# FT232.net
KiCad netlist of a schematic drawn in Altium Designer
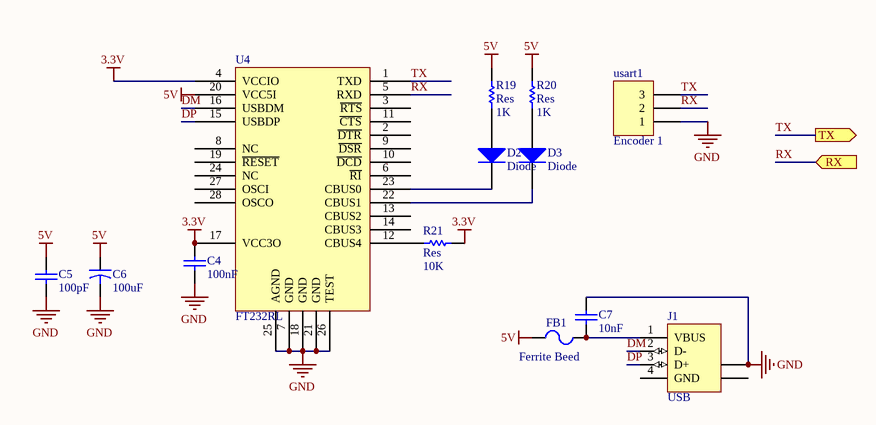
[diagram p0: FT232.SchDoc]

(export (version "E")
  (design (tool "Eeschema 10.0.6"))
  (components
    (comp (ref "C4")
      (value "100nF")
      (footprint "2012[0805]")
      (description "Capacitor")
      (fields (field (name "Comment") "Cap_UP") (field (name "PUBLISHER") "Altium Limited"))
      (libsource (lib "KN2CLib") (part "Cap_UP"))
    )
    (comp (ref "C5")
      (value "100pF")
      (footprint "2012[0805]")
      (description "Capacitor")
      (fields (field (name "Comment") "Cap_UP") (field (name "PUBLISHER") "Altium Limited"))
      (libsource (lib "KN2CLib") (part "Cap_UP"))
    )
    (comp (ref "C6")
      (value "100uF")
      (footprint "7343")
      (description "Capacitor")
      (fields (field (name "Comment") "Cap_El") (field (name "PUBLISHER") "Altium Limited"))
      (libsource (lib "KN2CLib") (part "Cap_El"))
    )
    (comp (ref "C7")
      (value "10nF")
      (footprint "2012[0805]")
      (description "Capacitor")
      (fields (field (name "Comment") "Cap_UP") (field (name "PUBLISHER") "Altium Limited"))
      (libsource (lib "KN2CLib") (part "Cap_UP"))
    )
    (comp (ref "D2")
      (value "Diode")
      (footprint "2012[0805]")
      (description "1 Amp General Purpose Rectifier")
      (fields (field (name "PUBLISHER") "Altium Limited"))
      (libsource (lib "KN2CLib") (part "Diode"))
    )
    (comp (ref "D3")
      (value "Diode")
      (footprint "2012[0805]")
      (description "1 Amp General Purpose Rectifier")
      (fields (field (name "PUBLISHER") "Altium Limited"))
      (libsource (lib "KN2CLib") (part "Diode"))
    )
    (comp (ref "FB1")
      (value "Ferrite Beed")
      (footprint "2012[0805]")
      (fields (field (name "PUBLISHER") "Altium Limited"))
      (libsource (lib "KN2CLib") (part "Ferrite Beed"))
    )
    (comp (ref "J1")
      (value "USB")
      (footprint "USB_MINI")
      (description "USB 1.1, Right Angle, Thru-Hole, A Type, Receptacle, 4 Position, Black")
      (fields (field (name "PUBLISHER") "Altium Limited"))
      (libsource (lib "KN2CLib") (part "USB"))
    )
    (comp (ref "R19")
      (value "Res")
      (footprint "2012[0805]")
      (description "Semiconductor Resistor")
      (fields (field (name "ALTIUM_VALUE") "1K") (field (name "PUBLISHER") "Altium Limited"))
      (libsource (lib "KN2CLib") (part "Res"))
    )
    (comp (ref "R20")
      (value "Res")
      (footprint "2012[0805]")
      (description "Semiconductor Resistor")
      (fields (field (name "ALTIUM_VALUE") "1K") (field (name "PUBLISHER") "Altium Limited"))
      (libsource (lib "KN2CLib") (part "Res"))
    )
    (comp (ref "R21")
      (value "Res")
      (footprint "2012[0805]")
      (description "Semiconductor Resistor")
      (fields (field (name "ALTIUM_VALUE") "10K") (field (name "PUBLISHER") "Altium Limited"))
      (libsource (lib "KN2CLib") (part "Res"))
    )
    (comp (ref "U4") (value "FT232RL") (footprint "SSOP28") (libsource (lib "KN2CLib") (part "FT232RL")))
    (comp (ref "usart1")
      (value "Encoder 1")
      (footprint "HDR1X3")
      (description "Header, 3-Pin")
      (fields (field (name "PUBLISHER") "Altium Limited"))
      (libsource (lib "KN2CLib") (part "Header 3"))
    )
  )
  (nets
    (net (code "1") (name "/DM") (class "Default")
      (node (ref "J1") (pin "2") (pinfunction "D-_2") (pintype "bidirectional"))
      (node (ref "U4") (pin "16") (pinfunction "USBDM_16") (pintype "passive"))
    )
    (net (code "2") (name "/DP") (class "Default")
      (node (ref "J1") (pin "3") (pinfunction "D+_3") (pintype "bidirectional"))
      (node (ref "U4") (pin "15") (pinfunction "USBDP_15") (pintype "passive"))
    )
    (net (code "3") (name "/RX") (class "Default")
      (node (ref "U4") (pin "5") (pinfunction "RXD_5") (pintype "passive"))
      (node (ref "usart1") (pin "2") (pinfunction "2_2") (pintype "passive"))
    )
    (net (code "4") (name "/TX") (class "Default")
      (node (ref "U4") (pin "1") (pinfunction "TXD_1") (pintype "passive"))
      (node (ref "usart1") (pin "3") (pinfunction "3_3") (pintype "passive"))
    )
    (net (code "5") (name "3.3V") (class "Default")
      (node (ref "C4") (pin "2") (pinfunction "2_2") (pintype "passive"))
      (node (ref "R21") (pin "2") (pinfunction "2_2") (pintype "passive"))
      (node (ref "U4") (pin "17") (pinfunction "VCC3O_17") (pintype "passive"))
      (node (ref "U4") (pin "4") (pinfunction "VCCIO_4") (pintype "passive"))
    )
    (net (code "6") (name "5V") (class "Default")
      (node (ref "C5") (pin "2") (pinfunction "2_2") (pintype "passive"))
      (node (ref "C6") (pin "1") (pinfunction "1_1") (pintype "passive"))
      (node (ref "FB1") (pin "1") (pinfunction "1_1") (pintype "passive"))
      (node (ref "R19") (pin "2") (pinfunction "2_2") (pintype "passive"))
      (node (ref "R20") (pin "2") (pinfunction "2_2") (pintype "passive"))
      (node (ref "U4") (pin "20") (pinfunction "VCC5I_20") (pintype "passive"))
    )
    (net (code "7") (name "GND") (class "Default")
      (node (ref "C4") (pin "1") (pinfunction "1_1") (pintype "passive"))
      (node (ref "C5") (pin "1") (pinfunction "1_1") (pintype "passive"))
      (node (ref "C6") (pin "2") (pinfunction "2_2") (pintype "passive"))
      (node (ref "C7") (pin "1") (pinfunction "1_1") (pintype "passive"))
      (node (ref "J1") (pin "5") (pinfunction "SHLD_5") (pintype "passive"))
      (node (ref "U4") (pin "18") (pinfunction "GND_18") (pintype "passive"))
      (node (ref "U4") (pin "21") (pinfunction "GND_21") (pintype "passive"))
      (node (ref "U4") (pin "25") (pinfunction "AGND_25") (pintype "passive"))
      (node (ref "U4") (pin "26") (pinfunction "TEST_26") (pintype "passive"))
      (node (ref "U4") (pin "7") (pinfunction "GND_7") (pintype "passive"))
      (node (ref "usart1") (pin "1") (pinfunction "1_1") (pintype "passive"))
    )
    (net (code "8") (name "Net-(D2-A)") (class "Default")
      (node (ref "D2") (pin "1") (pinfunction "A_1") (pintype "passive"))
      (node (ref "R19") (pin "1") (pinfunction "1_1") (pintype "passive"))
    )
    (net (code "9") (name "Net-(D2-K)") (class "Default")
      (node (ref "D2") (pin "2") (pinfunction "K_2") (pintype "passive"))
      (node (ref "U4") (pin "23") (pinfunction "CBUS0_23") (pintype "passive"))
    )
    (net (code "10") (name "Net-(D3-A)") (class "Default")
      (node (ref "D3") (pin "1") (pinfunction "A_1") (pintype "passive"))
      (node (ref "R20") (pin "1") (pinfunction "1_1") (pintype "passive"))
    )
    (net (code "11") (name "Net-(D3-K)") (class "Default")
      (node (ref "D3") (pin "2") (pinfunction "K_2") (pintype "passive"))
      (node (ref "U4") (pin "22") (pinfunction "CBUS1_22") (pintype "passive"))
    )
    (net (code "12") (name "Net-(J1-VBUS)") (class "Default")
      (node (ref "C7") (pin "2") (pinfunction "2_2") (pintype "passive"))
      (node (ref "FB1") (pin "2") (pinfunction "2_2") (pintype "passive"))
      (node (ref "J1") (pin "1") (pinfunction "VBUS_1") (pintype "power_in"))
    )
    (net (code "13") (name "Net-(U4-CBUS4)") (class "Default")
      (node (ref "R21") (pin "1") (pinfunction "1_1") (pintype "passive"))
      (node (ref "U4") (pin "12") (pinfunction "CBUS4_12") (pintype "passive"))
    )
    (net (code "14") (name "unconnected-(J1-GND-Pad4)") (class "Default")
      (node (ref "J1") (pin "4") (pinfunction "GND_4") (pintype "power_in"))
    )
    (net (code "15") (name "unconnected-(J1-SHLD-Pad6)") (class "Default")
      (node (ref "J1") (pin "6") (pinfunction "SHLD_6") (pintype "passive"))
    )
    (net (code "16") (name "unconnected-(U4-CBUS2-Pad13)") (class "Default")
      (node (ref "U4") (pin "13") (pinfunction "CBUS2_13") (pintype "passive"))
    )
    (net (code "17") (name "unconnected-(U4-CBUS3-Pad14)") (class "Default")
      (node (ref "U4") (pin "14") (pinfunction "CBUS3_14") (pintype "passive"))
    )
    (net (code "18") (name "unconnected-(U4-NC-Pad8)") (class "Default")
      (node (ref "U4") (pin "8") (pinfunction "NC_8") (pintype "passive"))
    )
    (net (code "19") (name "unconnected-(U4-NC-Pad24)") (class "Default")
      (node (ref "U4") (pin "24") (pinfunction "NC_24") (pintype "passive"))
    )
    (net (code "20") (name "unconnected-(U4-OSCI-Pad27)") (class "Default")
      (node (ref "U4") (pin "27") (pinfunction "OSCI_27") (pintype "passive"))
    )
    (net (code "21") (name "unconnected-(U4-OSCO-Pad28)") (class "Default")
      (node (ref "U4") (pin "28") (pinfunction "OSCO_28") (pintype "passive"))
    )
    (net (code "22") (name "unconnected-(U4-~{CTS}-Pad11)") (class "Default")
      (node (ref "U4") (pin "11") (pinfunction "~{CTS}_11") (pintype "passive"))
    )
    (net (code "23") (name "unconnected-(U4-~{DCD}-Pad10)") (class "Default")
      (node (ref "U4") (pin "10") (pinfunction "~{DCD}_10") (pintype "passive"))
    )
    (net (code "24") (name "unconnected-(U4-~{DSR}-Pad9)") (class "Default")
      (node (ref "U4") (pin "9") (pinfunction "~{DSR}_9") (pintype "passive"))
    )
    (net (code "25") (name "unconnected-(U4-~{DTR}-Pad2)") (class "Default")
      (node (ref "U4") (pin "2") (pinfunction "~{DTR}_2") (pintype "passive"))
    )
    (net (code "26") (name "unconnected-(U4-~{RESET}-Pad19)") (class "Default")
      (node (ref "U4") (pin "19") (pinfunction "~{RESET}_19") (pintype "passive"))
    )
    (net (code "27") (name "unconnected-(U4-~{RI}-Pad6)") (class "Default")
      (node (ref "U4") (pin "6") (pinfunction "~{RI}_6") (pintype "passive"))
    )
    (net (code "28") (name "unconnected-(U4-~{RTS}-Pad3)") (class "Default")
      (node (ref "U4") (pin "3") (pinfunction "~{RTS}_3") (pintype "passive"))
    )
  )
)
